# gps.net
KiCad netlist of a schematic drawn in Altium Designer
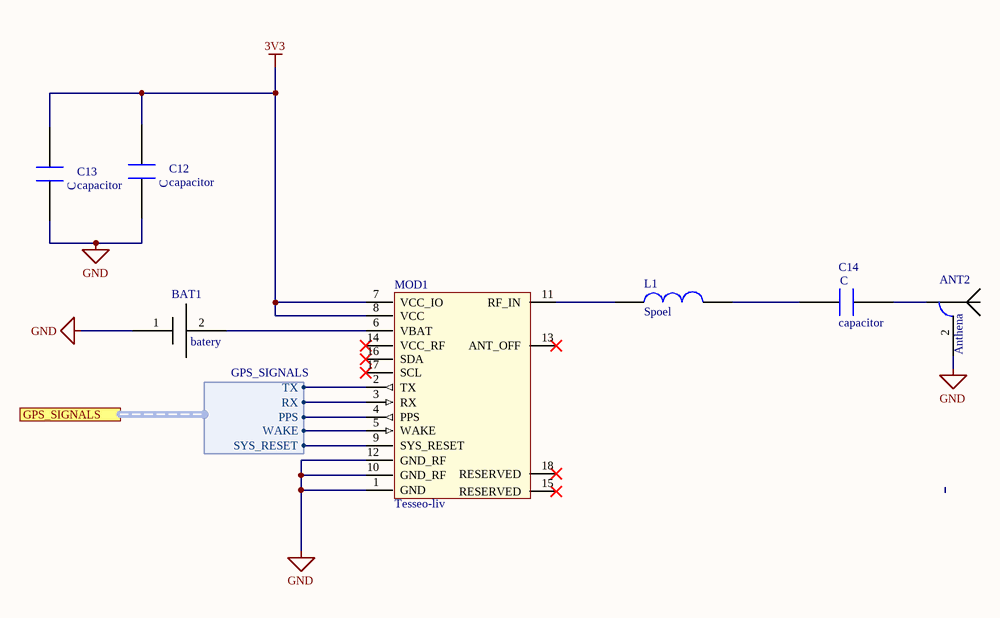
[diagram p0: gps.SchDoc]

(export (version "E")
  (design (tool "Eeschema 10.0.6"))
  (components
    (comp (ref "ANT2") (value "Anthena") (libsource (lib "pasives") (part "Anthena")))
    (comp (ref "BAT1") (value "batery") (libsource (lib "conector's_and_TP") (part "batery")))
    (comp (ref "C12")
      (value "capacitor")
      (footprint "CAPC1005X04L")
      (libsource (lib "pasives") (part "capacitor"))
    )
    (comp (ref "C13")
      (value "capacitor")
      (footprint "CAPC1005X04L")
      (libsource (lib "pasives") (part "capacitor"))
    )
    (comp (ref "C14")
      (value "capacitor")
      (footprint "CAPC1005X04L")
      (libsource (lib "pasives") (part "capacitor"))
    )
    (comp (ref "L1")
      (value "Spoel")
      (footprint "Coilcraft , XFL4020-102")
      (libsource (lib "pasives") (part "Spoel"))
    )
    (comp (ref "MOD1") (value "Tesseo-liv") (libsource (lib "halfgelijders") (part "Tesseo-liv")))
  )
  (nets
    (net (code "2") (name "/PPS") (class "Default")
      (node (ref "MOD1") (pin "4") (pinfunction "PPS_4") (pintype "output"))
    )
    (net (code "3") (name "/RX") (class "Default")
      (node (ref "MOD1") (pin "3") (pinfunction "RX_3") (pintype "input"))
    )
    (net (code "4") (name "/SYS_RESET") (class "Default")
      (node (ref "MOD1") (pin "9") (pinfunction "SYS_RESET_9") (pintype "passive"))
    )
    (net (code "5") (name "/TX") (class "Default")
      (node (ref "MOD1") (pin "2") (pinfunction "TX_2") (pintype "output"))
    )
    (net (code "6") (name "/WAKE") (class "Default")
      (node (ref "MOD1") (pin "5") (pinfunction "WAKE_5") (pintype "input"))
    )
    (net (code "8") (name "3V3") (class "Default")
      (node (ref "C12") (pin "1") (pinfunction "1_1") (pintype "passive"))
      (node (ref "C13") (pin "1") (pinfunction "1_1") (pintype "passive"))
      (node (ref "MOD1") (pin "7") (pinfunction "VCC_IO_7") (pintype "power_in"))
      (node (ref "MOD1") (pin "8") (pinfunction "VCC_8") (pintype "passive"))
    )
    (net (code "9") (name "GND") (class "Default")
      (node (ref "ANT2") (pin "2") (pinfunction "2_2") (pintype "passive"))
      (node (ref "BAT1") (pin "1") (pinfunction "1_1") (pintype "passive"))
      (node (ref "C12") (pin "2") (pinfunction "2_2") (pintype "passive"))
      (node (ref "C13") (pin "2") (pinfunction "2_2") (pintype "passive"))
      (node (ref "MOD1") (pin "1") (pinfunction "GND_1") (pintype "power_in"))
      (node (ref "MOD1") (pin "10") (pinfunction "GND_RF_10") (pintype "power_in"))
      (node (ref "MOD1") (pin "12") (pinfunction "GND_RF_12") (pintype "power_in"))
    )
    (net (code "10") (name "Net-(ANT2-Pad1)") (class "Default")
      (node (ref "ANT2") (pin "1") (pinfunction "1_1") (pintype "passive"))
      (node (ref "C14") (pin "1") (pinfunction "1_1") (pintype "passive"))
    )
    (net (code "11") (name "Net-(C14-Pad2)") (class "Default")
      (node (ref "C14") (pin "2") (pinfunction "2_2") (pintype "passive"))
      (node (ref "L1") (pin "1") (pinfunction "1_1") (pintype "passive"))
    )
    (net (code "12") (name "Net-(MOD1-RF_IN)") (class "Default")
      (node (ref "L1") (pin "2") (pinfunction "2_2") (pintype "passive"))
      (node (ref "MOD1") (pin "11") (pinfunction "RF_IN_11") (pintype "passive"))
    )
    (net (code "13") (name "Net-(MOD1-VBAT)") (class "Default")
      (node (ref "BAT1") (pin "2") (pinfunction "2_2") (pintype "passive"))
      (node (ref "MOD1") (pin "6") (pinfunction "VBAT_6") (pintype "power_in"))
    )
    (net (code "14") (name "unconnected-(MOD1-ANT_OFF-Pad13)") (class "Default")
      (node (ref "MOD1") (pin "13") (pinfunction "ANT_OFF_13") (pintype "passive+no_connect"))
    )
    (net (code "15") (name "unconnected-(MOD1-RESERVED-Pad15)") (class "Default")
      (node (ref "MOD1") (pin "15") (pinfunction "RESERVED_15") (pintype "passive+no_connect"))
    )
    (net (code "16") (name "unconnected-(MOD1-RESERVED-Pad18)") (class "Default")
      (node (ref "MOD1") (pin "18") (pinfunction "RESERVED_18") (pintype "passive+no_connect"))
    )
    (net (code "17") (name "unconnected-(MOD1-SCL-Pad17)") (class "Default")
      (node (ref "MOD1") (pin "17") (pinfunction "SCL_17") (pintype "open_collector+no_connect"))
    )
    (net (code "18") (name "unconnected-(MOD1-SDA-Pad16)") (class "Default")
      (node (ref "MOD1") (pin "16") (pinfunction "SDA_16") (pintype "open_collector+no_connect"))
    )
    (net (code "19") (name "unconnected-(MOD1-VCC_RF-Pad14)") (class "Default")
      (node (ref "MOD1") (pin "14") (pinfunction "VCC_RF_14") (pintype "power_in+no_connect"))
    )
  )
)
